# Power_External_Connectors.net
KiCad netlist of a schematic drawn in Altium Designer
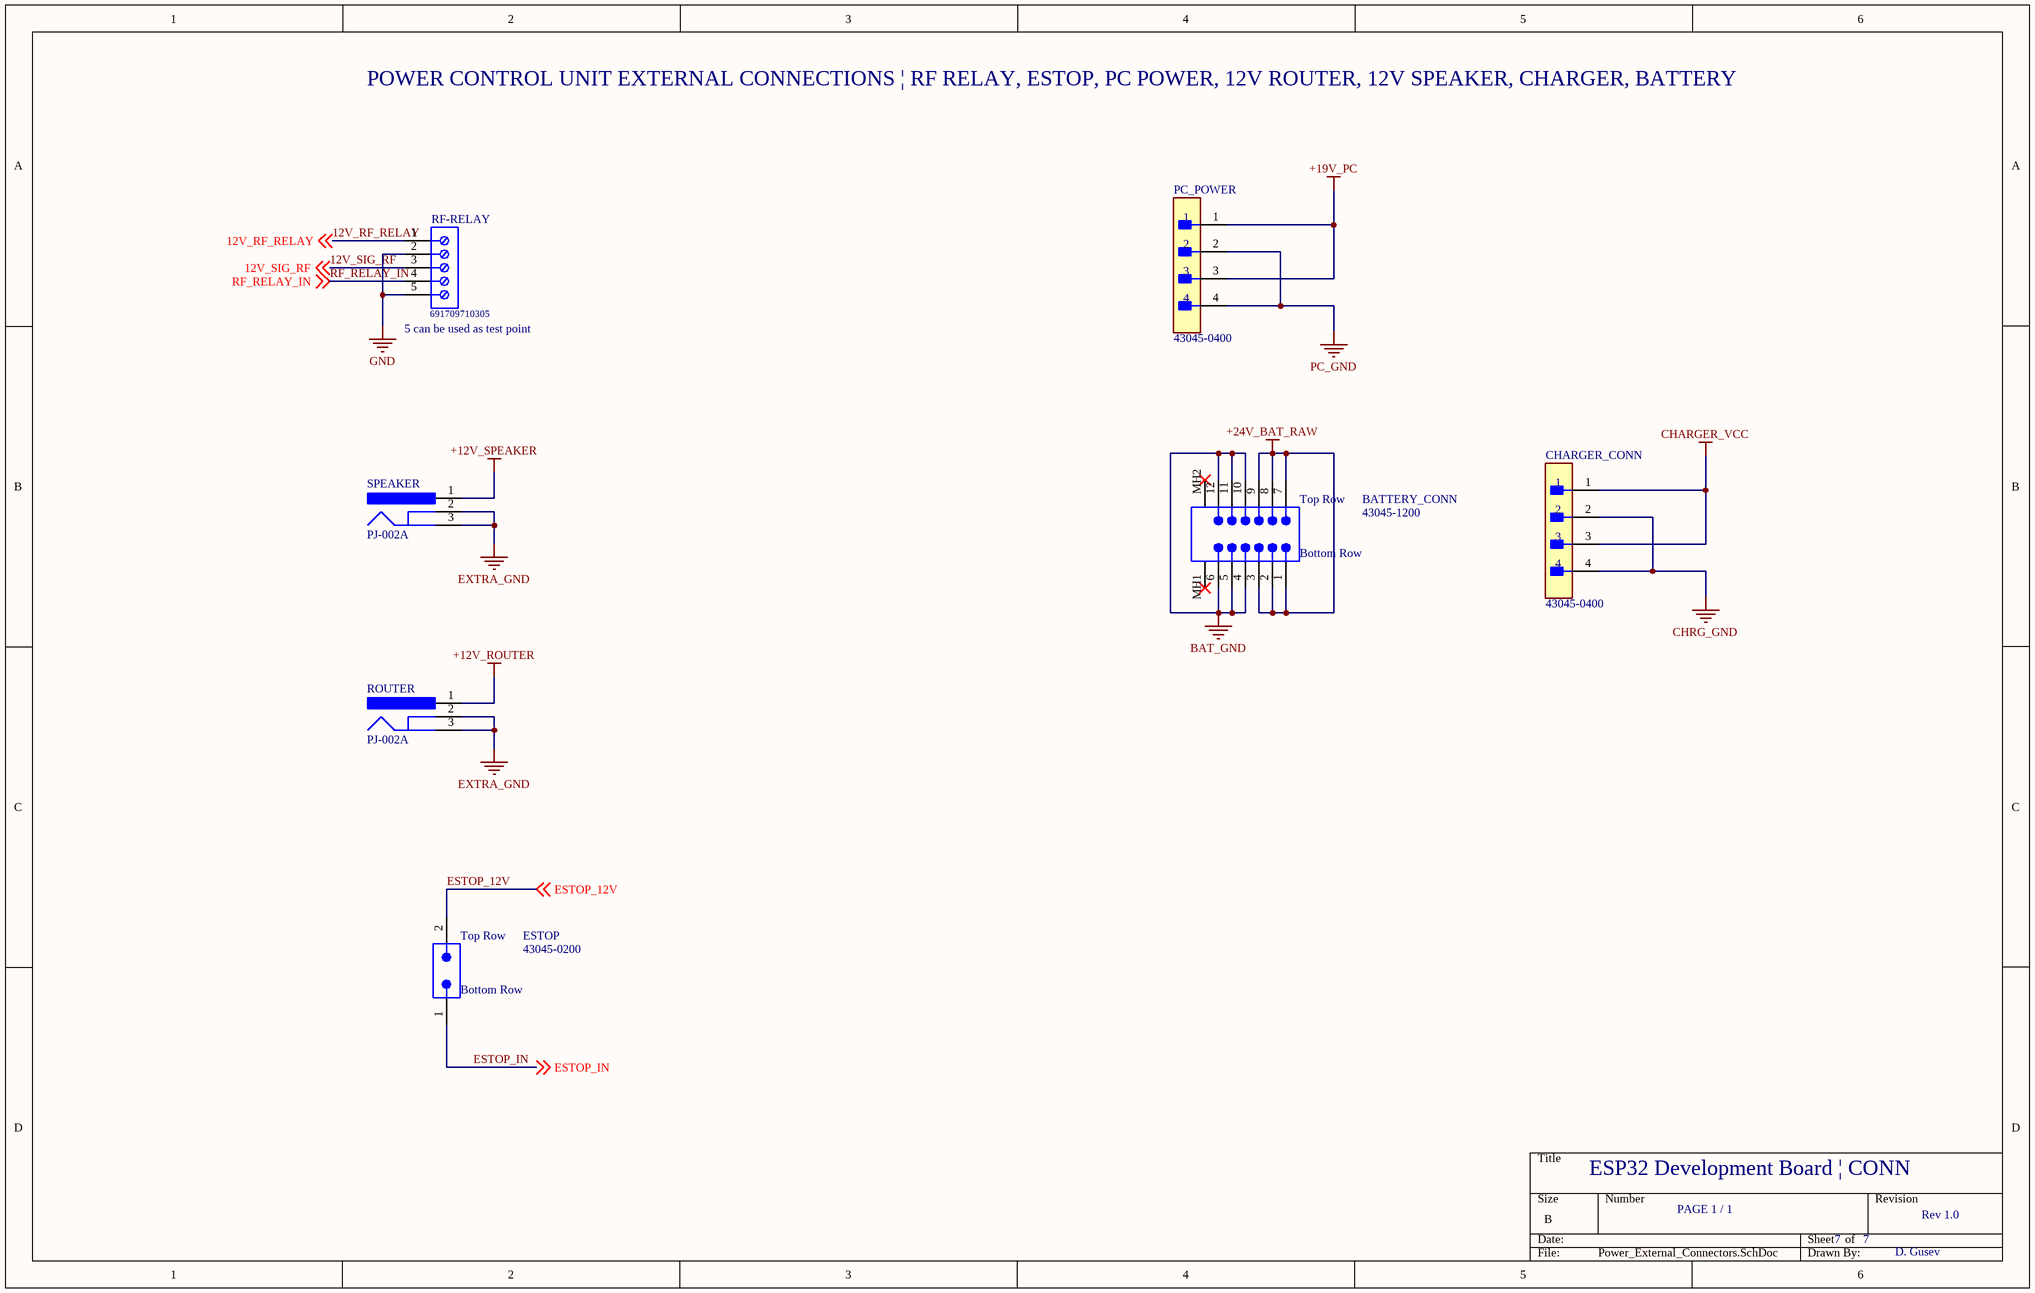
[diagram p0: Power_External_Connectors.SchDoc]

(export (version "E")
  (design (tool "Eeschema 10.0.6"))
  (components
    (comp (ref "BATTERY_CONN")
      (value "43045-1200")
      (footprint "MOLX-43045-1200")
      (fields (field (name "PARTNUMBER") "43045-0812"))
      (libsource (lib "ANTS-MotherBoard-B1") (part "Molex 0430451-200"))
    )
    (comp (ref "CHARGER_CONN")
      (value "43045-0400")
      (footprint "FP-43045-0400-MFG")
      (description "CONN HEADER R/A 4POS 3MM")
      (fields
        (field (name "MANUFACTURER") "Molex")
        (field (name "OCTOPART") "https://octopart.com/43045-0400-molex-287063")
      )
      (libsource (lib "Altium Content Vault") (part "c01754ab0efc13afb7424b896f394ef"))
    )
    (comp (ref "ESTOP")
      (value "43045-0200")
      (footprint "MOLX-43045-0200")
      (fields (field (name "PARTNUMBER") "43045-0812"))
      (libsource (lib "ANTS-MotherBoard-B1") (part "Molex 0430450-200"))
    )
    (comp (ref "PC_POWER")
      (value "43045-0400")
      (footprint "FP-43045-0400-MFG")
      (description "CONN HEADER R/A 4POS 3MM")
      (fields
        (field (name "MANUFACTURER") "Molex")
        (field (name "OCTOPART") "https://octopart.com/43045-0400-molex-287063")
      )
      (libsource (lib "Altium Content Vault") (part "c01754ab0efc13afb7424b896f394ef"))
    )
    (comp (ref "RF-RELAY")
      (value "691709710305")
      (footprint "691709710305")
      (description "Serie 7097 - 5.00 mm Horizontal Entry SMT with Pressure Clamp WR-TBL, 5 pin")
      (fields (field (name "MANUFACTURER") "Wurth Elektronik") (field (name "PUBLISHER") "WurthElektronik"))
      (libsource (lib "Altium Content Vault") (part "WE-CN-1P-F-TB5"))
    )
    (comp (ref "ROUTER")
      (value "PJ-002A")
      (footprint "CUI-PJ-002A_V")
      (fields (field (name "MANUFACTURER") "CUIInc."))
      (libsource (lib "Altium Content Vault") (part "JACK-2CD3-RN"))
    )
    (comp (ref "SPEAKER")
      (value "PJ-002A")
      (footprint "CUI-PJ-002A_V")
      (fields (field (name "MANUFACTURER") "CUIInc."))
      (libsource (lib "Altium Content Vault") (part "JACK-2CD3-RN"))
    )
  )
  (nets
    (net (code "1") (name "+12V_ROUTER") (class "Default")
      (node (ref "ROUTER") (pin "1") (pinfunction "1_1") (pintype "passive"))
    )
    (net (code "2") (name "+12V_SPEAKER") (class "Default")
      (node (ref "SPEAKER") (pin "1") (pinfunction "1_1") (pintype "passive"))
    )
    (net (code "3") (name "+19V_PC") (class "Default")
      (node (ref "PC_POWER") (pin "1") (pinfunction "1_1") (pintype "passive"))
      (node (ref "PC_POWER") (pin "3") (pinfunction "3_3") (pintype "passive"))
    )
    (net (code "4") (name "+24V_BAT_RAW") (class "Default")
      (node (ref "BATTERY_CONN") (pin "1") (pinfunction "1_1") (pintype "passive"))
      (node (ref "BATTERY_CONN") (pin "2") (pinfunction "2_2") (pintype "passive"))
      (node (ref "BATTERY_CONN") (pin "3") (pinfunction "3_3") (pintype "passive"))
      (node (ref "BATTERY_CONN") (pin "7") (pinfunction "7_7") (pintype "passive"))
      (node (ref "BATTERY_CONN") (pin "8") (pinfunction "8_8") (pintype "passive"))
      (node (ref "BATTERY_CONN") (pin "9") (pinfunction "9_9") (pintype "passive"))
    )
    (net (code "5") (name "12V_RF_RELAY") (class "Default")
      (node (ref "RF-RELAY") (pin "1") (pinfunction "1_1") (pintype "passive"))
    )
    (net (code "6") (name "12V_SIG_RF") (class "Default")
      (node (ref "RF-RELAY") (pin "3") (pinfunction "3_3") (pintype "passive"))
    )
    (net (code "7") (name "BAT_GND") (class "Default")
      (node (ref "BATTERY_CONN") (pin "10") (pinfunction "10_10") (pintype "passive"))
      (node (ref "BATTERY_CONN") (pin "11") (pinfunction "11_11") (pintype "passive"))
      (node (ref "BATTERY_CONN") (pin "12") (pinfunction "12_12") (pintype "passive"))
      (node (ref "BATTERY_CONN") (pin "4") (pinfunction "4_4") (pintype "passive"))
      (node (ref "BATTERY_CONN") (pin "5") (pinfunction "5_5") (pintype "passive"))
      (node (ref "BATTERY_CONN") (pin "6") (pinfunction "6_6") (pintype "passive"))
    )
    (net (code "8") (name "CHARGER_VCC") (class "Default")
      (node (ref "CHARGER_CONN") (pin "1") (pinfunction "1_1") (pintype "passive"))
      (node (ref "CHARGER_CONN") (pin "3") (pinfunction "3_3") (pintype "passive"))
    )
    (net (code "9") (name "CHRG_GND") (class "Default")
      (node (ref "CHARGER_CONN") (pin "2") (pinfunction "2_2") (pintype "passive"))
      (node (ref "CHARGER_CONN") (pin "4") (pinfunction "4_4") (pintype "passive"))
    )
    (net (code "10") (name "ESTOP_12V") (class "Default")
      (node (ref "ESTOP") (pin "2") (pinfunction "2_2") (pintype "passive"))
    )
    (net (code "11") (name "ESTOP_IN") (class "Default")
      (node (ref "ESTOP") (pin "1") (pinfunction "1_1") (pintype "passive"))
    )
    (net (code "12") (name "EXTRA_GND") (class "Default")
      (node (ref "ROUTER") (pin "2") (pinfunction "2_2") (pintype "passive"))
      (node (ref "ROUTER") (pin "3") (pinfunction "3_3") (pintype "passive"))
      (node (ref "SPEAKER") (pin "2") (pinfunction "2_2") (pintype "passive"))
      (node (ref "SPEAKER") (pin "3") (pinfunction "3_3") (pintype "passive"))
    )
    (net (code "13") (name "GND") (class "Default")
      (node (ref "RF-RELAY") (pin "2") (pinfunction "2_2") (pintype "passive"))
      (node (ref "RF-RELAY") (pin "5") (pinfunction "5_5") (pintype "passive"))
    )
    (net (code "14") (name "PC_GND") (class "Default")
      (node (ref "PC_POWER") (pin "2") (pinfunction "2_2") (pintype "passive"))
      (node (ref "PC_POWER") (pin "4") (pinfunction "4_4") (pintype "passive"))
    )
    (net (code "15") (name "RF_RELAY_IN") (class "Default")
      (node (ref "RF-RELAY") (pin "4") (pinfunction "4_4") (pintype "passive"))
    )
    (net (code "16") (name "unconnected-(BATTERY_CONN-PadMH1)") (class "Default")
      (node (ref "BATTERY_CONN") (pin "MH1") (pinfunction "MH1_MH1") (pintype "passive+no_connect"))
    )
    (net (code "17") (name "unconnected-(BATTERY_CONN-PadMH2)") (class "Default")
      (node (ref "BATTERY_CONN") (pin "MH2") (pinfunction "MH2_MH2") (pintype "passive+no_connect"))
    )
  )
)
